# Sheet1.net
KiCad netlist of a schematic drawn in Altium Designer
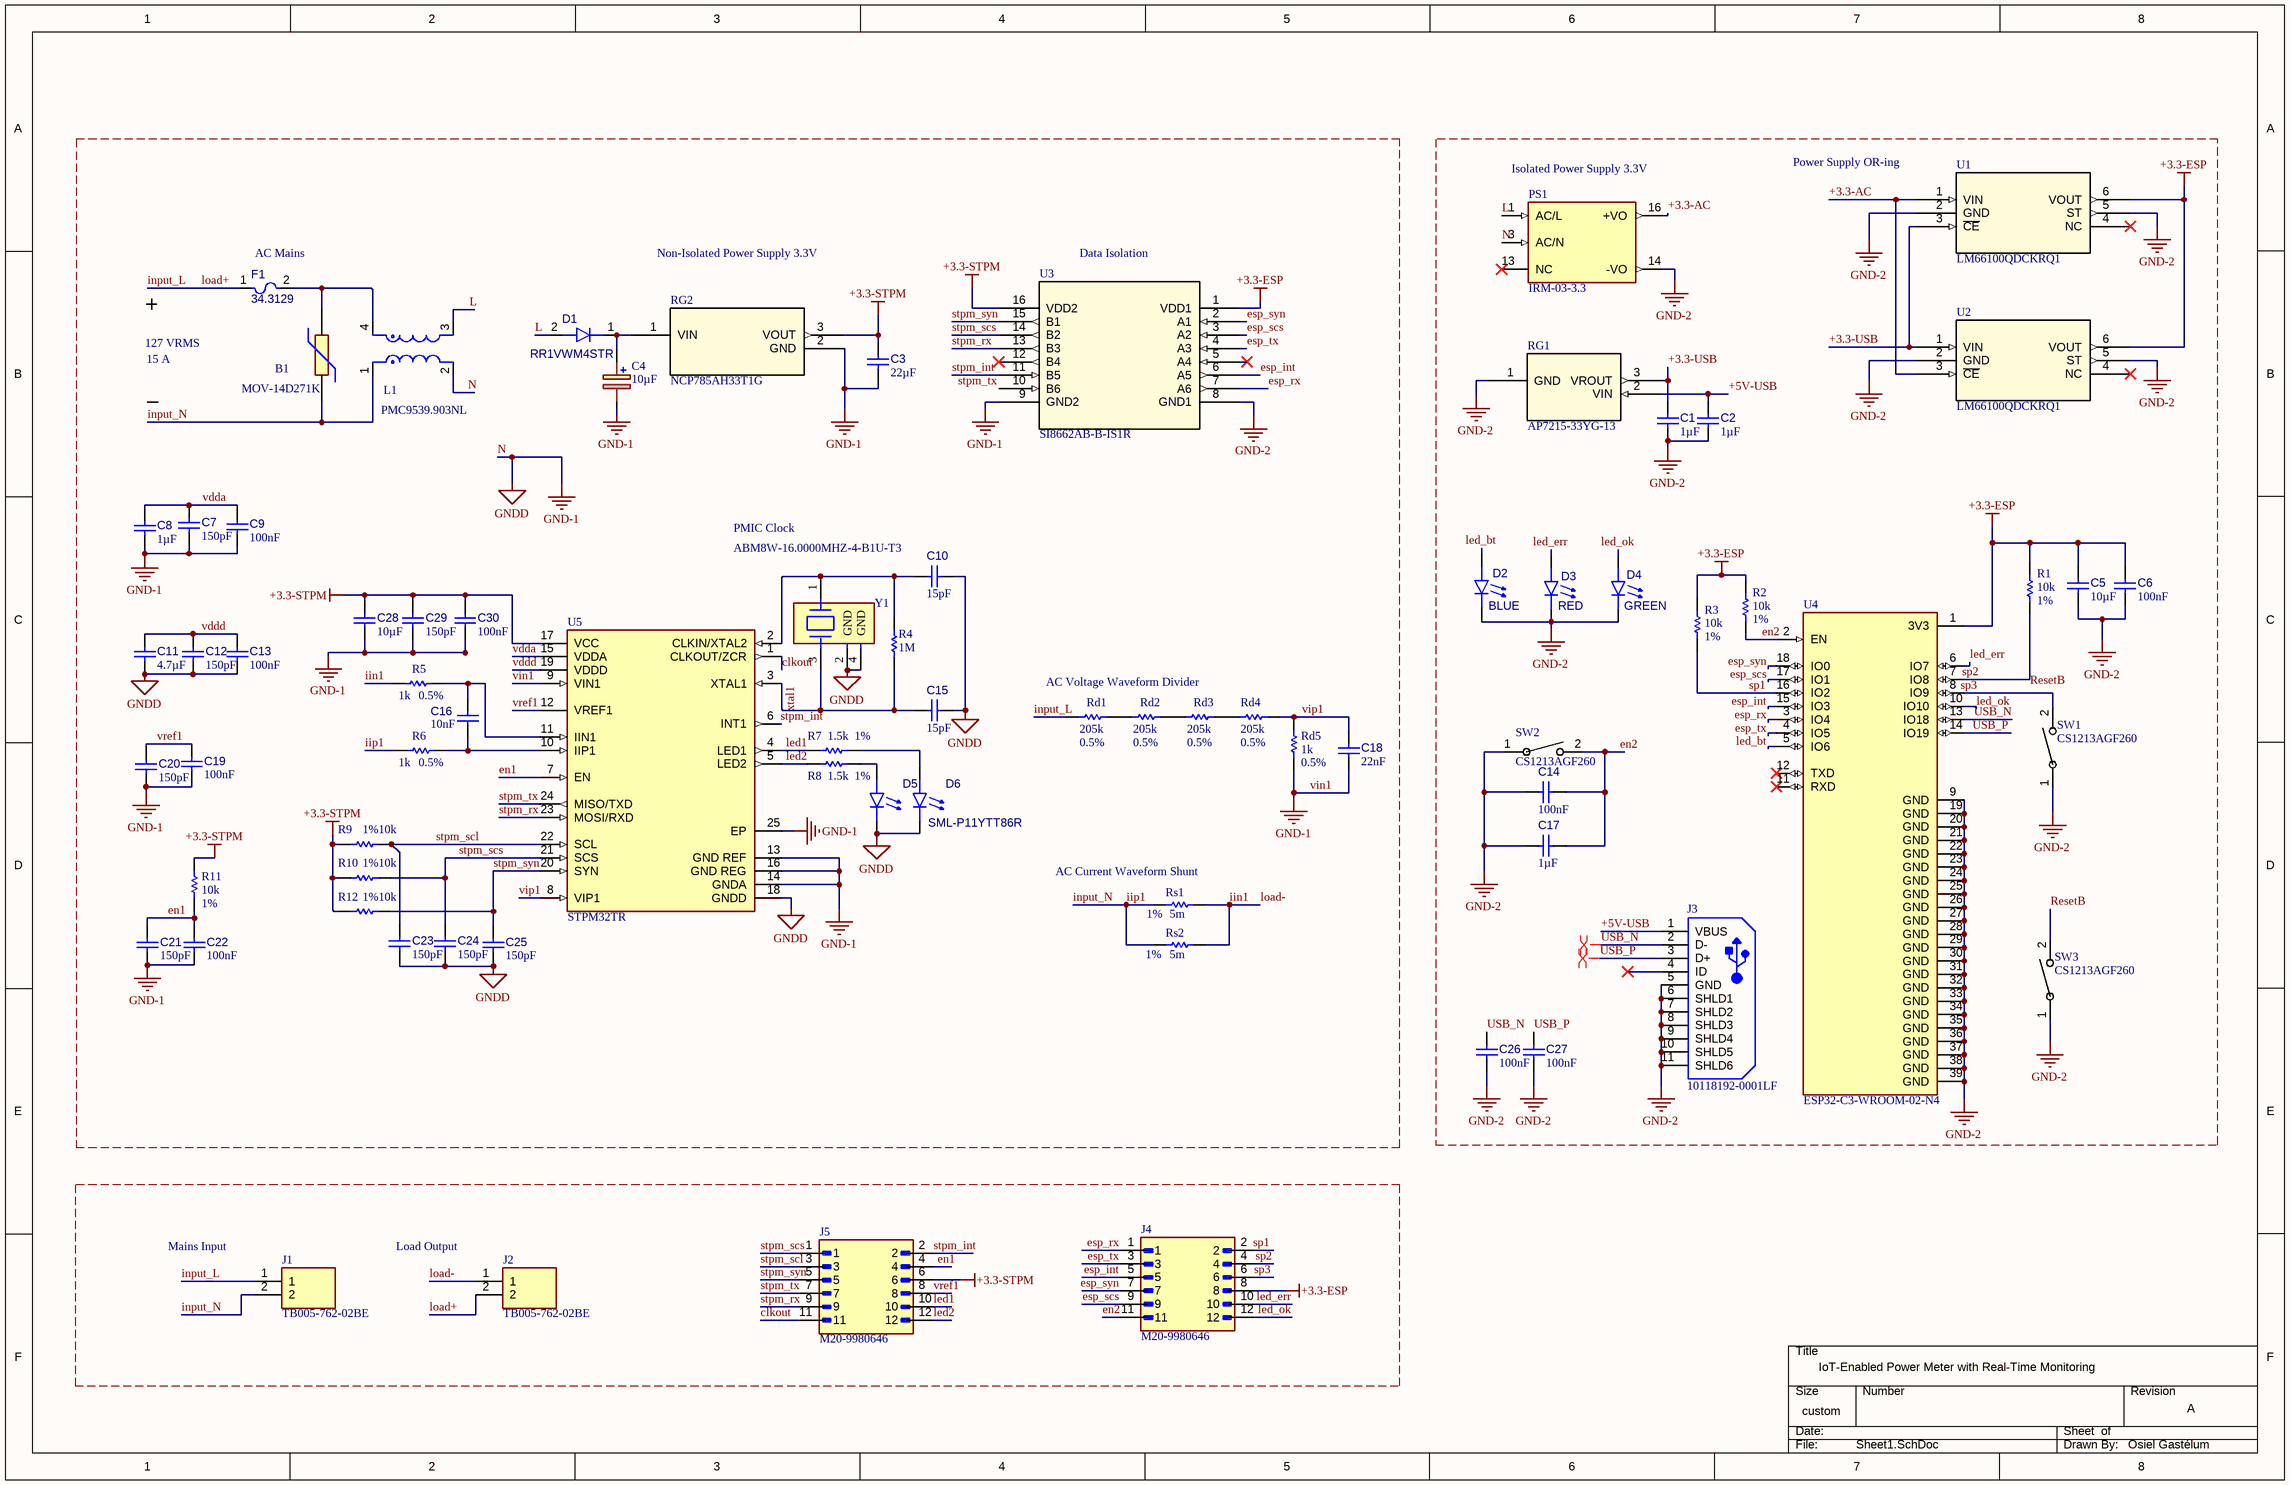
[diagram p0: Sheet1.SchDoc]

(export (version "E")
  (design (tool "Eeschema 10.0.6"))
  (components
    (comp (ref "B1")
      (value "MOV-14D271K")
      (footprint "MOV14D271K")
      (description "Var MOV 175VAC/225VDC 4500A 270V Thru-Hole Radial Bulk")
      (libsource (lib "Workspace") (part "MOV-14D271K"))
    )
    (comp (ref "C1")
      (value "1µF")
      (footprint "CAP_0805_N")
      (description "Multilayer Ceramic Capacitors MLCC – SMD/SMT; KEMET; C0805C105K3RACTU; 1 µF; 0805; 25 V; 25 V")
      (fields (field (name "TOLERANCE") "10%") (field (name "Comment") "CAP-NP-2"))
      (libsource (lib "Workspace") (part "CAP-NP-2"))
    )
    (comp (ref "C2")
      (value "1µF")
      (footprint "CAP_0805_N")
      (description "Multilayer Ceramic Capacitors MLCC – SMD/SMT; KEMET; C0805C105K3RACTU; 1 µF; 0805; 25 V; 25 V")
      (fields (field (name "TOLERANCE") "10%") (field (name "Comment") "CAP-NP-2"))
      (libsource (lib "Workspace") (part "CAP-NP-2"))
    )
    (comp (ref "C3")
      (value "22µF")
      (footprint "CAP_0805_N")
      (description "25V 22uF X5R ±20% 0805 Multilayer Ceramic Capacitors MLCC - SMD/SMT ROHS")
      (fields (field (name "TOLERANCE") "20%") (field (name "Comment") "GRM21BR61E226ME44L"))
      (libsource (lib "Workspace") (part "CAP-NP-2"))
    )
    (comp (ref "C4")
      (value "10µF")
      (footprint "CAPAE1030X1400N")
      (fields (field (name "Comment") "AEF1013100M400R"))
      (libsource (lib "Workspace") (part "AEF1013100M400R-Symbol-1"))
    )
    (comp (ref "C5")
      (value "10µF")
      (footprint "CAP_0805_N")
      (description "0805 C 10UF Ceramic Multilayer Capacitor, 25 VDC, +85DEGC, X5R Dielec, +/-10%")
      (fields (field (name "TOLERANCE") "10%") (field (name "Comment") "CAP-NP-2"))
      (libsource (lib "Workspace") (part "CAP-NP-2"))
    )
    (comp (ref "C6")
      (value "100nF")
      (footprint "CAP_0805_N")
      (description "25V 100nF X7R ±10% 0805 Multilayer Ceramic Capacitors MLCC - SMD/SMT ROHS")
      (fields (field (name "TOLERANCE") "10%") (field (name "Comment") "CAP-NP-2"))
      (libsource (lib "Workspace") (part "CAP-NP-2"))
    )
    (comp (ref "C7")
      (value "150pF")
      (footprint "CAP_0805_N")
      (description "SMD Comm C0G 0805 (2012Metric) Ceramic Capacitor 0.079Lx0.049W 2.00mmx1.25mm C0G NP0 ±10% 150pF")
      (fields (field (name "TOLERANCE") "10%") (field (name "Comment") "CAP-NP-2"))
      (libsource (lib "Workspace") (part "CAP-NP-2"))
    )
    (comp (ref "C8")
      (value "1µF")
      (footprint "CAP_0805_N")
      (description "Multilayer Ceramic Capacitors MLCC – SMD/SMT; KEMET; C0805C105K3RACTU; 1 µF; 0805; 25 V; 25 V")
      (fields (field (name "TOLERANCE") "10%") (field (name "Comment") "CAP-NP-2"))
      (libsource (lib "Workspace") (part "CAP-NP-2"))
    )
    (comp (ref "C9")
      (value "100nF")
      (footprint "CAP_0805_N")
      (description "25V 100nF X7R ±10% 0805 Multilayer Ceramic Capacitors MLCC - SMD/SMT ROHS")
      (fields (field (name "TOLERANCE") "10%") (field (name "Comment") "CAP-NP-2"))
      (libsource (lib "Workspace") (part "CAP-NP-2"))
    )
    (comp (ref "C10")
      (value "15pF")
      (footprint "CAP_0805_N")
      (fields (field (name "TOLERANCE") "5%") (field (name "Comment") "CAP-NP-2"))
      (libsource (lib "Workspace") (part "CAP-NP-2"))
    )
    (comp (ref "C11")
      (value "4.7µF")
      (footprint "CAP_0805_N")
      (fields (field (name "Comment") "CAP-NP-2"))
      (libsource (lib "Workspace") (part "CAP-NP-2"))
    )
    (comp (ref "C12")
      (value "150pF")
      (footprint "CAP_0805_N")
      (description "SMD Comm C0G 0805 (2012Metric) Ceramic Capacitor 0.079Lx0.049W 2.00mmx1.25mm C0G NP0 ±10% 150pF")
      (fields (field (name "TOLERANCE") "10%") (field (name "Comment") "CAP-NP-2"))
      (libsource (lib "Workspace") (part "CAP-NP-2"))
    )
    (comp (ref "C13")
      (value "100nF")
      (footprint "CAP_0805_N")
      (description "25V 100nF X7R ±10% 0805 Multilayer Ceramic Capacitors MLCC - SMD/SMT ROHS")
      (fields (field (name "TOLERANCE") "10%") (field (name "Comment") "CAP-NP-2"))
      (libsource (lib "Workspace") (part "CAP-NP-2"))
    )
    (comp (ref "C14")
      (value "100nF")
      (footprint "CAP_0805_N")
      (description "25V 100nF X7R ±10% 0805 Multilayer Ceramic Capacitors MLCC - SMD/SMT ROHS")
      (fields (field (name "TOLERANCE") "10%") (field (name "Comment") "CAP-NP-2"))
      (libsource (lib "Workspace") (part "CAP-NP-2"))
    )
    (comp (ref "C15")
      (value "15pF")
      (footprint "CAP_0805_N")
      (fields (field (name "TOLERANCE") "5%"))
      (libsource (lib "Workspace") (part "CAP-NP-2"))
    )
    (comp (ref "C16")
      (value "10nF")
      (footprint "CAP_0805_N")
      (fields (field (name "Comment") "C0805C103J3GECAUTO"))
      (libsource (lib "Workspace") (part "CAP-NP-2"))
    )
    (comp (ref "C17")
      (value "1µF")
      (footprint "CAP_0805_N")
      (description "Multilayer Ceramic Capacitors MLCC – SMD/SMT; KEMET; C0805C105K3RACTU; 1 µF; 0805; 25 V; 25 V")
      (fields (field (name "TOLERANCE") "10%") (field (name "Comment") "CAP-NP-2"))
      (libsource (lib "Workspace") (part "CAP-NP-2"))
    )
    (comp (ref "C18")
      (value "22nF")
      (footprint "CAP_0805_N")
      (fields (field (name "Comment") "C0805C223J3GEC7210"))
      (libsource (lib "Workspace") (part "CAP-NP-2"))
    )
    (comp (ref "C19")
      (value "100nF")
      (footprint "CAP_0805_N")
      (description "25V 100nF X7R ±10% 0805 Multilayer Ceramic Capacitors MLCC - SMD/SMT ROHS")
      (fields (field (name "TOLERANCE") "10%") (field (name "Comment") "CAP-NP-2"))
      (libsource (lib "Workspace") (part "CAP-NP-2"))
    )
    (comp (ref "C20")
      (value "150pF")
      (footprint "CAP_0805_N")
      (description "SMD Comm C0G 0805 (2012Metric) Ceramic Capacitor 0.079Lx0.049W 2.00mmx1.25mm C0G NP0 ±10% 150pF")
      (fields (field (name "TOLERANCE") "10%") (field (name "Comment") "CAP-NP-2"))
      (libsource (lib "Workspace") (part "CAP-NP-2"))
    )
    (comp (ref "C21")
      (value "150pF")
      (footprint "CAP_0805_N")
      (description "SMD Comm C0G 0805 (2012Metric) Ceramic Capacitor 0.079Lx0.049W 2.00mmx1.25mm C0G NP0 ±10% 150pF")
      (fields (field (name "TOLERANCE") "10%") (field (name "Comment") "CAP-NP-2"))
      (libsource (lib "Workspace") (part "CAP-NP-2"))
    )
    (comp (ref "C22")
      (value "100nF")
      (footprint "CAP_0805_N")
      (description "25V 100nF X7R ±10% 0805 Multilayer Ceramic Capacitors MLCC - SMD/SMT ROHS")
      (fields (field (name "TOLERANCE") "10%") (field (name "Comment") "CAP-NP-2"))
      (libsource (lib "Workspace") (part "CAP-NP-2"))
    )
    (comp (ref "C23")
      (value "150pF")
      (footprint "CAP_0805_N")
      (description "SMD Comm C0G 0805 (2012Metric) Ceramic Capacitor 0.079Lx0.049W 2.00mmx1.25mm C0G NP0 ±10% 150pF")
      (fields (field (name "TOLERANCE") "10%") (field (name "Comment") "CAP-NP-2"))
      (libsource (lib "Workspace") (part "CAP-NP-2"))
    )
    (comp (ref "C24")
      (value "150pF")
      (footprint "CAP_0805_N")
      (description "SMD Comm C0G 0805 (2012Metric) Ceramic Capacitor 0.079Lx0.049W 2.00mmx1.25mm C0G NP0 ±10% 150pF")
      (fields (field (name "TOLERANCE") "10%") (field (name "Comment") "CAP-NP-2"))
      (libsource (lib "Workspace") (part "CAP-NP-2"))
    )
    (comp (ref "C25")
      (value "150pF")
      (footprint "CAP_0805_N")
      (description "SMD Comm C0G 0805 (2012Metric) Ceramic Capacitor 0.079Lx0.049W 2.00mmx1.25mm C0G NP0 ±10% 150pF")
      (fields (field (name "TOLERANCE") "10%") (field (name "Comment") "CAP-NP-2"))
      (libsource (lib "Workspace") (part "CAP-NP-2"))
    )
    (comp (ref "C26")
      (value "100nF")
      (footprint "CAP_0805_N")
      (description "25V 100nF X7R ±10% 0805 Multilayer Ceramic Capacitors MLCC - SMD/SMT ROHS")
      (fields (field (name "TOLERANCE") "10%") (field (name "Comment") "CAP-NP-2"))
      (libsource (lib "Workspace") (part "CAP-NP-2"))
    )
    (comp (ref "C27")
      (value "100nF")
      (footprint "CAP_0805_N")
      (description "25V 100nF X7R ±10% 0805 Multilayer Ceramic Capacitors MLCC - SMD/SMT ROHS")
      (fields (field (name "TOLERANCE") "10%") (field (name "Comment") "CAP-NP-2"))
      (libsource (lib "Workspace") (part "CAP-NP-2"))
    )
    (comp (ref "C28")
      (value "10µF")
      (footprint "CAP_0805_N")
      (description "0805 C 10UF Ceramic Multilayer Capacitor, 25 VDC, +85DEGC, X5R Dielec, +/-10%")
      (fields (field (name "TOLERANCE") "10%") (field (name "Comment") "C0805C106K3PACTU"))
      (libsource (lib "Workspace") (part "CAP-NP-2"))
    )
    (comp (ref "C29")
      (value "150pF")
      (footprint "CAP_0805_N")
      (description "SMD Comm C0G 0805 (2012Metric) Ceramic Capacitor 0.079Lx0.049W 2.00mmx1.25mm C0G NP0 ±10% 150pF")
      (fields (field (name "TOLERANCE") "10%") (field (name "Comment") "C0805C151K3GACTU"))
      (libsource (lib "Workspace") (part "CAP-NP-2"))
    )
    (comp (ref "C30")
      (value "100nF")
      (footprint "CAP_0805_N")
      (description "25V 100nF X7R ±10% 0805 Multilayer Ceramic Capacitors MLCC - SMD/SMT ROHS")
      (fields (field (name "TOLERANCE") "10%") (field (name "Comment") "C0805C104K3RACTU"))
      (libsource (lib "Workspace") (part "CAP-NP-2"))
    )
    (comp (ref "D1")
      (value "RR1VWM4STR")
      (footprint "PMDE_ROM")
      (description "Rectifier Diode, 1 Phase, 1 Element, 1A, 400V V(RRM), Silicon")
      (libsource (lib "Workspace") (part "DIODE-2"))
    )
    (comp (ref "D2")
      (value "BLUE")
      (footprint "WL-SMCW_0805")
      (description "Led, Blue, 470 Nm, 3.2 V, 30 Ma, 145 Mcd Rohs Compliant: Yes")
      (libsource (lib "Workspace") (part "DIODE-LED-2"))
    )
    (comp (ref "D3")
      (value "RED")
      (footprint "WL-SMCW_0805")
      (description "LED Uni-Color Red 630nm 2-Pin Chip 0805(2012Metric) T/R")
      (libsource (lib "Workspace") (part "DIODE-LED-2"))
    )
    (comp (ref "D4")
      (value "GREEN")
      (footprint "WL-SMCW_0805")
      (description "0805, Green Typ.(@20mA): 520nm, 450mcd, 3.2V, 140Â° InGaN")
      (fields (field (name "MP") "150080GS75000") (field (name "MF") "Wurth Electronics"))
      (libsource (lib "Workspace") (part "DIODE-LED-2"))
    )
    (comp (ref "D5")
      (value "SML-P11DTT86R")
      (footprint "LED_SML-P11D_ROM")
      (description "LED orange LED0402 wavelength 605nm light intensity 7.3mcd Front Mounting")
      (libsource (lib "Workspace") (part "DIODE-LED-2"))
    )
    (comp (ref "D6")
      (value "SML-P11YTT86R")
      (footprint "LED_SML-P11D_ROM")
      (description "LED Uni-Color Yellow Chip LED 2-Pin 0402 T/R")
      (libsource (lib "Workspace") (part "DIODE-LED-2"))
    )
    (comp (ref "F1")
      (value "34.3129")
      (footprint "3132873")
      (description "Fuse 5 x 20 mm, 16 A, T, 250 V (AC), 160 A breaking capacity, 0034.3129")
      (libsource (lib "Workspace") (part "FUSE-2"))
    )
    (comp (ref "J1")
      (value "TB005-762-02BE")
      (footprint "CUI_TB005-762-02BE")
      (description "2~24 Poles, Screw Type, Horizontal, 7.62 Pitch, 26~10 (AWG), Terminal Block Connector")
      (fields (field (name "MF") "Same Sky"))
      (libsource (lib "Workspace") (part "TB005-762-02BE"))
    )
    (comp (ref "J2")
      (value "TB005-762-02BE")
      (footprint "CUI_TB005-762-02BE")
      (description "2~24 Poles, Screw Type, Horizontal, 7.62 Pitch, 26~10 (AWG), Terminal Block Connector")
      (fields (field (name "MF") "Same Sky"))
      (libsource (lib "Workspace") (part "TB005-762-02BE"))
    )
    (comp (ref "J3")
      (value "10118192-0001LF")
      (footprint "FCI-10118192-0001LF-5_V")
      (description "Usb Connector, 5 Contact(S), Female, Right Angle, Surface Mount Terminal, Locking, Receptacle")
      (libsource (lib "Workspace") (part "USB-5-6SHLD"))
    )
    (comp (ref "J4")
      (value "M20-9980646")
      (footprint "HARWIN_M20-9980646")
      (description "Board Connector, 12 Contact(s), 1 Row(s), Male, Straight, Solder Terminal")
      (libsource (lib "Workspace") (part "M20-9980646"))
    )
    (comp (ref "J5")
      (value "M20-9980646")
      (footprint "HARWIN_M20-9980646")
      (description "Board Connector, 12 Contact(s), 1 Row(s), Male, Straight, Solder Terminal")
      (libsource (lib "Workspace") (part "M20-9980646"))
    )
    (comp (ref "L1")
      (value "PMC9539.903NL")
      (footprint "PMC9539_PUL")
      (description "250惟@2.1MHz 1.3m惟 2 Plugin, 19.6x17.8mm Common Mode Filters ROHS")
      (libsource (lib "Workspace") (part "TFORM-4"))
    )
    (comp (ref "PS1")
      (value "IRM-03-3.3")
      (footprint "CONV_IRM-03-3.3")
      (description "DC-DC Converter, PCB Mnt, 3W, 3.3V@600mA, IRM-03 Series")
      (fields (field (name "MF") "MEAN WELL USA Inc."))
      (libsource (lib "Workspace") (part "IRM-03-3.3"))
    )
    (comp (ref "R1")
      (value "10k")
      (footprint "RES_0805_N")
      (description "Res Thick Film 0805 10K Ohm 1% 1/8W ±50ppm/°C Molded SMD Paper T/R")
      (fields (field (name "TOLERANCE") "1%") (field (name "Comment") "RE0805FRE0710KL"))
      (libsource (lib "Workspace") (part "RES"))
    )
    (comp (ref "R2")
      (value "10k")
      (footprint "RES_0805_N")
      (description "Res Thick Film 0805 10K Ohm 1% 1/8W ±50ppm/°C Molded SMD Paper T/R")
      (fields (field (name "TOLERANCE") "1%") (field (name "Comment") "RE0805FRE0710KL"))
      (libsource (lib "Workspace") (part "RES"))
    )
    (comp (ref "R3")
      (value "10k")
      (footprint "RES_0805_N")
      (description "Res Thick Film 0805 10K Ohm 1% 1/8W ±50ppm/°C Molded SMD Paper T/R")
      (fields (field (name "TOLERANCE") "1%") (field (name "Comment") "RE0805FRE0710KL"))
      (libsource (lib "Workspace") (part "RES"))
    )
    (comp (ref "R4")
      (value "1M")
      (footprint "RES_0805_N")
      (description "Res, 1M, 1%, 0.125W, 0805, Thick Film Rohs Compliant: Yes")
      (fields (field (name "TOLERANCE") "1%") (field (name "Comment") "RE0805FRE071ML"))
      (libsource (lib "Workspace") (part "RES"))
    )
    (comp (ref "R5")
      (value "1k")
      (footprint "RES_0805_N")
      (description "125mW Thin Film Resistor 150V ±0.5% ±25ppm/℃ 1kΩ 0805 Chip Resistor - Surface Mount ROHS")
      (fields (field (name "TOLERANCE") "0.5%") (field (name "Comment") "RT0805DRD071KL"))
      (libsource (lib "Workspace") (part "RES"))
    )
    (comp (ref "R6")
      (value "1k")
      (footprint "RES_0805_N")
      (description "125mW Thin Film Resistor 150V ±0.5% ±25ppm/℃ 1kΩ 0805 Chip Resistor - Surface Mount ROHS")
      (fields (field (name "TOLERANCE") "0.5%") (field (name "Comment") "RT0805DRD071KL"))
      (libsource (lib "Workspace") (part "RES"))
    )
    (comp (ref "R7")
      (value "1.5k")
      (footprint "RES_0805_N")
      (description "Chip Resistor Precision Grade Thick Film 0805 1.5kOhm 1% Paper T/R")
      (fields (field (name "TOLERANCE") "1%") (field (name "Comment") "RE0805FRE071K5L"))
      (libsource (lib "Workspace") (part "RES"))
    )
    (comp (ref "R8")
      (value "1.5k")
      (footprint "RES_0805_N")
      (description "Chip Resistor Precision Grade Thick Film 0805 1.5kOhm 1% Paper T/R")
      (fields (field (name "TOLERANCE") "1%") (field (name "Comment") "RE0805FRE071K5L"))
      (libsource (lib "Workspace") (part "RES"))
    )
    (comp (ref "R9")
      (value "10k")
      (footprint "RES_0805_N")
      (description "Res Thick Film 0805 10K Ohm 1% 1/8W ±50ppm/°C Molded SMD Paper T/R")
      (fields (field (name "TOLERANCE") "1%") (field (name "Comment") "RE0805FRE0710KL"))
      (libsource (lib "Workspace") (part "RES"))
    )
    (comp (ref "R10")
      (value "10k")
      (footprint "RES_0805_N")
      (description "Res Thick Film 0805 10K Ohm 1% 1/8W ±50ppm/°C Molded SMD Paper T/R")
      (fields (field (name "TOLERANCE") "1%") (field (name "Comment") "RE0805FRE0710KL"))
      (libsource (lib "Workspace") (part "RES"))
    )
    (comp (ref "R11")
      (value "10k")
      (footprint "RES_0805_N")
      (description "Res Thick Film 0805 10K Ohm 1% 1/8W ±50ppm/°C Molded SMD Paper T/R")
      (fields (field (name "TOLERANCE") "1%") (field (name "Comment") "RE0805FRE0710KL"))
      (libsource (lib "Workspace") (part "RES"))
    )
    (comp (ref "R12")
      (value "10k")
      (footprint "RES_0805_N")
      (description "Res Thick Film 0805 10K Ohm 1% 1/8W ±50ppm/°C Molded SMD Paper T/R")
      (fields (field (name "TOLERANCE") "1%") (field (name "Comment") "RE0805FRE0710KL"))
      (libsource (lib "Workspace") (part "RES"))
    )
    (comp (ref "Rd1")
      (value "205k")
      (footprint "RES_0805_N")
      (description "Res Thin Film 0805 205K Ohm 0.5% 0.125W(1/8W) ±25ppm/C Pad SMD Automotive T/R")
      (fields (field (name "TOLERANCE") "0.5%") (field (name "Comment") "ERA-6AED2053V"))
      (libsource (lib "Workspace") (part "RES"))
    )
    (comp (ref "Rd2")
      (value "205k")
      (footprint "RES_0805_N")
      (description "Res Thin Film 0805 205K Ohm 0.5% 0.125W(1/8W) ±25ppm/C Pad SMD Automotive T/R")
      (fields (field (name "TOLERANCE") "0.5%") (field (name "Comment") "ERA-6AED2053V"))
      (libsource (lib "Workspace") (part "RES"))
    )
    (comp (ref "Rd3")
      (value "205k")
      (footprint "RES_0805_N")
      (description "Res Thin Film 0805 205K Ohm 0.5% 0.125W(1/8W) ±25ppm/C Pad SMD Automotive T/R")
      (fields (field (name "TOLERANCE") "0.5%") (field (name "Comment") "ERA-6AED2053V"))
      (libsource (lib "Workspace") (part "RES"))
    )
    (comp (ref "Rd4")
      (value "205k")
      (footprint "RES_0805_N")
      (description "Res Thin Film 0805 205K Ohm 0.5% 0.125W(1/8W) ±25ppm/C Pad SMD Automotive T/R")
      (fields (field (name "TOLERANCE") "0.5%") (field (name "Comment") "ERA-6AED2053V"))
      (libsource (lib "Workspace") (part "RES"))
    )
    (comp (ref "Rd5")
      (value "1k")
      (footprint "RES_0805_N")
      (description "125mW Thin Film Resistor 150V ±0.5% ±25ppm/℃ 1kΩ 0805 Chip Resistor - Surface Mount ROHS")
      (fields (field (name "TOLERANCE") "0.5%") (field (name "Comment") "RT0805DRD071KL"))
      (libsource (lib "Workspace") (part "RES"))
    )
    (comp (ref "RG1")
      (value "AP7215-33YG-13")
      (footprint "SOT-89-3_2P7X4P7_ONS-M")
      (description "Voltage Regulators, LDO, SOT89-3L 3.3V/0.6A 250MV 3.3-5.5V 1.2V")
      (libsource (lib "Workspace") (part "AP7215-33YG-13-Symbol-1"))
    )
    (comp (ref "RG2")
      (value "NCP785AH33T1G")
      (footprint "SOT-89-3_2P7X4P7_ONS-M")
      (description "NCP785A Series 3.3 V 10 mA High Performance Linear Regulator - SOT-89")
      (libsource (lib "Workspace") (part "NCP785AH33T1G-Symbol-1"))
    )
    (comp (ref "Rs1")
      (value "5m")
      (footprint "RESC6430X100N")
      (description "Fixed Resistor, 5W, 0.005ohm, 0.158V, 1% +/-Tol, 50ppm/Cel, Surface Mount, 2512")
      (fields (field (name "TOLERANCE") "1%") (field (name "Comment") "CSSU2512FT5L00"))
      (libsource (lib "Workspace") (part "RES"))
    )
    (comp (ref "Rs2")
      (value "5m")
      (footprint "RESC6430X100N")
      (description "Fixed Resistor, 5W, 0.005ohm, 0.158V, 1% +/-Tol, 50ppm/Cel, Surface Mount, 2512")
      (fields (field (name "TOLERANCE") "1%") (field (name "Comment") "CSSU2512FT5L00"))
      (libsource (lib "Workspace") (part "RES"))
    )
    (comp (ref "SW1")
      (value "CS1213AGF260")
      (footprint "SW_CS1213AGF260_CRS")
      (description "Description")
      (fields (field (name "COPYRIGHT") "Copyright (C) 2025 Ultra Librarian. All rights reserved."))
      (libsource (lib "Workspace") (part "CS1213AGF260"))
    )
    (comp (ref "SW2")
      (value "CS1213AGF260")
      (footprint "SW_CS1213AGF260_CRS")
      (description "Description")
      (fields (field (name "COPYRIGHT") "Copyright (C) 2025 Ultra Librarian. All rights reserved."))
      (libsource (lib "") (part "CS1213AGF260_1"))
    )
    (comp (ref "SW3")
      (value "CS1213AGF260")
      (footprint "SW_CS1213AGF260_CRS")
      (description "Description")
      (fields (field (name "COPYRIGHT") "Copyright (C) 2025 Ultra Librarian. All rights reserved."))
      (libsource (lib "Workspace") (part "CS1213AGF260"))
    )
    (comp (ref "U1")
      (value "LM66100QDCKRQ1")
      (footprint "SC70-6_DCK_TEX")
      (description "Automotive 1.5-V to 5.5-V, 1.5-A, 0.5-µA IQ ideal diode with integrated FET 6-SC70 -40 to 125")
      (libsource (lib "Workspace") (part "LM66100QDCKRQ1-Symbol-1"))
    )
    (comp (ref "U2")
      (value "LM66100QDCKRQ1")
      (footprint "SC70-6_DCK_TEX")
      (description "Automotive 1.5-V to 5.5-V, 1.5-A, 0.5-µA IQ ideal diode with integrated FET 6-SC70 -40 to 125")
      (libsource (lib "Workspace") (part "LM66100QDCKRQ1-Symbol-1"))
    )
    (comp (ref "U3")
      (value "SI8662AB-B-IS1R")
      (footprint "SOIC-16_SIL")
      (description "General Purpose tal Isolator 2500Vrms 6 Channel 1Mbps 35kV/µs CMTI 16-SOIC (0.154 , 3.90mm Width)")
      (libsource (lib "Workspace") (part "SI8662AB-B-IS1R"))
    )
    (comp (ref "U4")
      (value "ESP32-C3-WROOM-02-N4")
      (footprint "MODULE_ESP32-C3-WROOM-02-H4")
      (fields (field (name "MF") "Espressif Systems"))
      (libsource (lib "Workspace") (part "ESP32-C3-WROOM-02-N4"))
    )
    (comp (ref "U5")
      (value "STPM32TR")
      (footprint "FP-QFN24L-7596209-IPC_B")
      (description "STPM32 Series 3.3 V 4.3 mA 3.6 kHz Single Phase Metering IC - QFN-24")
      (libsource (lib "Workspace") (part "5b5f0ec8f2a583f794e357655103e6c"))
    )
    (comp (ref "Y1")
      (value "ABM8W-16.0000MHZ-4-B1U-T3")
      (footprint "FP-ABM8W-MFG")
      (description "Crystal 16MHz ±10ppm (Tol) ±10ppm (Stability) 4pF FUND 70Ohm 4-Pin SMD T/R")
      (libsource (lib "Workspace") (part "41079aabb0e87794b56622915be14ed"))
    )
  )
  (nets
    (net (code "1") (name "+3.3-ESP") (class "Default")
      (node (ref "C5") (pin "1") (pinfunction "1_1") (pintype "passive"))
      (node (ref "C6") (pin "2") (pinfunction "2_2") (pintype "passive"))
      (node (ref "J4") (pin "8") (pinfunction "8_8") (pintype "passive"))
      (node (ref "R1") (pin "1") (pinfunction "1_1") (pintype "passive"))
      (node (ref "R2") (pin "1") (pinfunction "1_1") (pintype "passive"))
      (node (ref "R3") (pin "1") (pinfunction "1_1") (pintype "passive"))
      (node (ref "U1") (pin "6") (pinfunction "VOUT_6") (pintype "output"))
      (node (ref "U2") (pin "6") (pinfunction "VOUT_6") (pintype "output"))
      (node (ref "U3") (pin "1") (pinfunction "VDD1_1") (pintype "power_in"))
      (node (ref "U4") (pin "1") (pinfunction "3V3_1") (pintype "power_in"))
    )
    (net (code "2") (name "+3.3-STPM") (class "Default")
      (node (ref "C28") (pin "2") (pinfunction "2_2") (pintype "passive"))
      (node (ref "C29") (pin "2") (pinfunction "2_2") (pintype "passive"))
      (node (ref "C3") (pin "2") (pinfunction "2_2") (pintype "passive"))
      (node (ref "C30") (pin "2") (pinfunction "2_2") (pintype "passive"))
      (node (ref "J5") (pin "6") (pinfunction "6_6") (pintype "passive"))
      (node (ref "R10") (pin "2") (pinfunction "2_2") (pintype "passive"))
      (node (ref "R11") (pin "2") (pinfunction "2_2") (pintype "passive"))
      (node (ref "R12") (pin "2") (pinfunction "2_2") (pintype "passive"))
      (node (ref "R9") (pin "2") (pinfunction "2_2") (pintype "passive"))
      (node (ref "RG2") (pin "3") (pinfunction "VOUT_3") (pintype "output"))
      (node (ref "U3") (pin "16") (pinfunction "VDD2_16") (pintype "power_in"))
      (node (ref "U5") (pin "17") (pinfunction "VCC_17") (pintype "power_in"))
    )
    (net (code "3") (name "/+3.3-AC") (class "Default")
      (node (ref "PS1") (pin "16") (pinfunction "+VO_16") (pintype "output"))
      (node (ref "U1") (pin "1") (pinfunction "VIN_1") (pintype "input"))
      (node (ref "U2") (pin "3") (pinfunction "~{CE}_3") (pintype "input"))
    )
    (net (code "4") (name "/+3.3-USB") (class "Default")
      (node (ref "C1") (pin "2") (pinfunction "2_2") (pintype "passive"))
      (node (ref "RG1") (pin "3") (pinfunction "VROUT_3") (pintype "output"))
      (node (ref "U1") (pin "3") (pinfunction "~{CE}_3") (pintype "input"))
      (node (ref "U2") (pin "1") (pinfunction "VIN_1") (pintype "input"))
    )
    (net (code "5") (name "/+5V-USB") (class "Default")
      (node (ref "C2") (pin "2") (pinfunction "2_2") (pintype "passive"))
      (node (ref "J3") (pin "1") (pinfunction "VBUS_1") (pintype "passive"))
      (node (ref "RG1") (pin "2") (pinfunction "VIN_2") (pintype "input"))
    )
    (net (code "6") (name "/L") (class "Default")
      (node (ref "D1") (pin "2") (pinfunction "A_2") (pintype "passive"))
      (node (ref "L1") (pin "3") (pinfunction "3_3") (pintype "passive"))
      (node (ref "PS1") (pin "1") (pinfunction "AC/L_1") (pintype "input"))
    )
    (net (code "7") (name "/ResetB") (class "Default")
      (node (ref "J4") (pin "4") (pinfunction "4_4") (pintype "passive"))
      (node (ref "R1") (pin "2") (pinfunction "2_2") (pintype "passive"))
      (node (ref "SW3") (pin "2") (pinfunction "2_2") (pintype "passive"))
      (node (ref "U4") (pin "7") (pinfunction "IO8_7") (pintype "bidirectional"))
    )
    (net (code "8") (name "/USB_N") (class "Default")
      (node (ref "C26") (pin "2") (pinfunction "2_2") (pintype "passive"))
      (node (ref "J3") (pin "2") (pinfunction "D-_2") (pintype "passive"))
      (node (ref "U4") (pin "13") (pinfunction "IO18_13") (pintype "bidirectional"))
    )
    (net (code "9") (name "/USB_P") (class "Default")
      (node (ref "C27") (pin "2") (pinfunction "2_2") (pintype "passive"))
      (node (ref "J3") (pin "3") (pinfunction "D+_3") (pintype "passive"))
      (node (ref "U4") (pin "14") (pinfunction "IO19_14") (pintype "bidirectional"))
    )
    (net (code "10") (name "/clkout") (class "Default")
      (node (ref "J5") (pin "11") (pinfunction "11_11") (pintype "passive"))
      (node (ref "U5") (pin "1") (pinfunction "CLKOUT/ZCR_1") (pintype "output"))
    )
    (net (code "11") (name "/en1") (class "Default")
      (node (ref "C21") (pin "2") (pinfunction "2_2") (pintype "passive"))
      (node (ref "C22") (pin "2") (pinfunction "2_2") (pintype "passive"))
      (node (ref "J5") (pin "4") (pinfunction "4_4") (pintype "passive"))
      (node (ref "R11") (pin "1") (pinfunction "1_1") (pintype "passive"))
      (node (ref "U5") (pin "7") (pinfunction "EN_7") (pintype "input"))
    )
    (net (code "12") (name "/en2") (class "Default")
      (node (ref "C14") (pin "1") (pinfunction "1_1") (pintype "passive"))
      (node (ref "C17") (pin "2") (pinfunction "2_2") (pintype "passive"))
      (node (ref "J4") (pin "11") (pinfunction "11_11") (pintype "passive"))
      (node (ref "R2") (pin "2") (pinfunction "2_2") (pintype "passive"))
      (node (ref "SW2") (pin "2") (pinfunction "2_2") (pintype "passive"))
      (node (ref "U4") (pin "2") (pinfunction "EN_2") (pintype "input"))
    )
    (net (code "13") (name "/esp_int") (class "Default")
      (node (ref "J4") (pin "5") (pinfunction "5_5") (pintype "passive"))
      (node (ref "U3") (pin "6") (pinfunction "A5_6") (pintype "output"))
      (node (ref "U4") (pin "15") (pinfunction "IO3_15") (pintype "bidirectional"))
    )
    (net (code "14") (name "/esp_rx") (class "Default")
      (node (ref "J4") (pin "1") (pinfunction "1_1") (pintype "passive"))
      (node (ref "U3") (pin "7") (pinfunction "A6_7") (pintype "output"))
      (node (ref "U4") (pin "3") (pinfunction "IO4_3") (pintype "bidirectional"))
    )
    (net (code "15") (name "/esp_scs") (class "Default")
      (node (ref "J4") (pin "9") (pinfunction "9_9") (pintype "passive"))
      (node (ref "U3") (pin "3") (pinfunction "A2_3") (pintype "input"))
      (node (ref "U4") (pin "17") (pinfunction "IO1_17") (pintype "bidirectional"))
    )
    (net (code "16") (name "/esp_syn") (class "Default")
      (node (ref "J4") (pin "7") (pinfunction "7_7") (pintype "passive"))
      (node (ref "U3") (pin "2") (pinfunction "A1_2") (pintype "input"))
      (node (ref "U4") (pin "18") (pinfunction "IO0_18") (pintype "bidirectional"))
    )
    (net (code "17") (name "/esp_tx") (class "Default")
      (node (ref "J4") (pin "3") (pinfunction "3_3") (pintype "passive"))
      (node (ref "U3") (pin "4") (pinfunction "A3_4") (pintype "input"))
      (node (ref "U4") (pin "4") (pinfunction "IO5_4") (pintype "bidirectional"))
    )
    (net (code "18") (name "/iin1") (class "Default")
      (node (ref "J2") (pin "1") (pinfunction "1_1") (pintype "passive"))
      (node (ref "R5") (pin "1") (pinfunction "1_1") (pintype "passive"))
      (node (ref "Rs1") (pin "2") (pinfunction "2_2") (pintype "passive"))
      (node (ref "Rs2") (pin "2") (pinfunction "2_2") (pintype "passive"))
    )
    (net (code "19") (name "/iip1") (class "Default")
      (node (ref "B1") (pin "1") (pinfunction "1_1") (pintype "passive"))
      (node (ref "J1") (pin "2") (pinfunction "2_2") (pintype "passive"))
      (node (ref "L1") (pin "1") (pinfunction "1_1") (pintype "passive"))
      (node (ref "R6") (pin "1") (pinfunction "1_1") (pintype "passive"))
      (node (ref "Rs1") (pin "1") (pinfunction "1_1") (pintype "passive"))
      (node (ref "Rs2") (pin "1") (pinfunction "1_1") (pintype "passive"))
    )
    (net (code "20") (name "/input_L") (class "Default")
      (node (ref "F1") (pin "1") (pinfunction "1_1") (pintype "passive"))
      (node (ref "J1") (pin "1") (pinfunction "1_1") (pintype "passive"))
      (node (ref "J2") (pin "2") (pinfunction "2_2") (pintype "passive"))
      (node (ref "Rd1") (pin "1") (pinfunction "1_1") (pintype "passive"))
    )
    (net (code "21") (name "/led1") (class "Default")
      (node (ref "J5") (pin "10") (pinfunction "10_10") (pintype "passive"))
      (node (ref "R7") (pin "1") (pinfunction "1_1") (pintype "passive"))
      (node (ref "U5") (pin "4") (pinfunction "LED1_4") (pintype "output"))
    )
    (net (code "22") (name "/led2") (class "Default")
      (node (ref "J5") (pin "12") (pinfunction "12_12") (pintype "passive"))
      (node (ref "R8") (pin "1") (pinfunction "1_1") (pintype "passive"))
      (node (ref "U5") (pin "5") (pinfunction "LED2_5") (pintype "output"))
    )
    (net (code "23") (name "/led_bt") (class "Default")
      (node (ref "D2") (pin "2") (pinfunction "A_2") (pintype "passive"))
      (node (ref "U4") (pin "5") (pinfunction "IO6_5") (pintype "bidirectional"))
    )
    (net (code "24") (name "/led_err") (class "Default")
      (node (ref "D3") (pin "2") (pinfunction "A_2") (pintype "passive"))
      (node (ref "J4") (pin "10") (pinfunction "10_10") (pintype "passive"))
      (node (ref "U4") (pin "6") (pinfunction "IO7_6") (pintype "bidirectional"))
    )
    (net (code "25") (name "/led_ok") (class "Default")
      (node (ref "D4") (pin "2") (pinfunction "A_2") (pintype "passive"))
      (node (ref "J4") (pin "12") (pinfunction "12_12") (pintype "passive"))
      (node (ref "U4") (pin "10") (pinfunction "IO10_10") (pintype "bidirectional"))
    )
    (net (code "26") (name "/sp1") (class "Default")
      (node (ref "J4") (pin "2") (pinfunction "2_2") (pintype "passive"))
      (node (ref "R3") (pin "2") (pinfunction "2_2") (pintype "passive"))
      (node (ref "U4") (pin "16") (pinfunction "IO2_16") (pintype "bidirectional"))
    )
    (net (code "27") (name "/sp3") (class "Default")
      (node (ref "J4") (pin "6") (pinfunction "6_6") (pintype "passive"))
      (node (ref "SW1") (pin "2") (pinfunction "2_2") (pintype "passive"))
      (node (ref "U4") (pin "8") (pinfunction "IO9_8") (pintype "bidirectional"))
    )
    (net (code "28") (name "/stpm_int") (class "Default")
      (node (ref "J5") (pin "2") (pinfunction "2_2") (pintype "passive"))
      (node (ref "U3") (pin "11") (pinfunction "B5_11") (pintype "input"))
      (node (ref "U5") (pin "6") (pinfunction "INT1_6") (pintype "output"))
    )
    (net (code "29") (name "/stpm_rx") (class "Default")
      (node (ref "J5") (pin "9") (pinfunction "9_9") (pintype "passive"))
      (node (ref "U3") (pin "13") (pinfunction "B3_13") (pintype "output"))
      (node (ref "U5") (pin "23") (pinfunction "MOSI/RXD_23") (pintype "input"))
    )
    (net (code "30") (name "/stpm_scl") (class "Default")
      (node (ref "C23") (pin "2") (pinfunction "2_2") (pintype "passive"))
      (node (ref "J5") (pin "3") (pinfunction "3_3") (pintype "passive"))
      (node (ref "R9") (pin "1") (pinfunction "1_1") (pintype "passive"))
      (node (ref "U5") (pin "22") (pinfunction "SCL_22") (pintype "input"))
    )
    (net (code "31") (name "/stpm_scs") (class "Default")
      (node (ref "C24") (pin "2") (pinfunction "2_2") (pintype "passive"))
      (node (ref "J5") (pin "1") (pinfunction "1_1") (pintype "passive"))
      (node (ref "R10") (pin "1") (pinfunction "1_1") (pintype "passive"))
      (node (ref "U3") (pin "14") (pinfunction "B2_14") (pintype "output"))
      (node (ref "U5") (pin "21") (pinfunction "SCS_21") (pintype "input"))
    )
    (net (code "32") (name "/stpm_syn") (class "Default")
      (node (ref "C25") (pin "2") (pinfunction "2_2") (pintype "passive"))
      (node (ref "J5") (pin "5") (pinfunction "5_5") (pintype "passive"))
      (node (ref "R12") (pin "1") (pinfunction "1_1") (pintype "passive"))
      (node (ref "U3") (pin "15") (pinfunction "B1_15") (pintype "output"))
      (node (ref "U5") (pin "20") (pinfunction "SYN_20") (pintype "input"))
    )
    (net (code "33") (name "/stpm_tx") (class "Default")
      (node (ref "J5") (pin "7") (pinfunction "7_7") (pintype "passive"))
      (node (ref "U3") (pin "10") (pinfunction "B6_10") (pintype "input"))
      (node (ref "U5") (pin "24") (pinfunction "MISO/TXD_24") (pintype "output"))
    )
    (net (code "34") (name "/vdda") (class "Default")
      (node (ref "C7") (pin "2") (pinfunction "2_2") (pintype "passive"))
      (node (ref "C8") (pin "2") (pinfunction "2_2") (pintype "passive"))
      (node (ref "C9") (pin "2") (pinfunction "2_2") (pintype "passive"))
      (node (ref "U5") (pin "15") (pinfunction "VDDA_15") (pintype "power_in"))
    )
    (net (code "35") (name "/vddd") (class "Default")
      (node (ref "C11") (pin "2") (pinfunction "2_2") (pintype "passive"))
      (node (ref "C12") (pin "2") (pinfunction "2_2") (pintype "passive"))
      (node (ref "C13") (pin "2") (pinfunction "2_2") (pintype "passive"))
      (node (ref "U5") (pin "19") (pinfunction "VDDD_19") (pintype "power_in"))
    )
    (net (code "36") (name "/vip1") (class "Default")
      (node (ref "C18") (pin "2") (pinfunction "2_2") (pintype "passive"))
      (node (ref "Rd4") (pin "1") (pinfunction "1_1") (pintype "passive"))
      (node (ref "Rd5") (pin "1") (pinfunction "1_1") (pintype "passive"))
      (node (ref "U5") (pin "8") (pinfunction "VIP1_8") (pintype "input"))
    )
    (net (code "37") (name "/vref1") (class "Default")
      (node (ref "C19") (pin "2") (pinfunction "2_2") (pintype "passive"))
      (node (ref "C20") (pin "2") (pinfunction "2_2") (pintype "passive"))
      (node (ref "J5") (pin "8") (pinfunction "8_8") (pintype "passive"))
      (node (ref "U5") (pin "12") (pinfunction "VREF1_12") (pintype "power_in"))
    )
    (net (code "38") (name "/xtal1") (class "Default")
      (node (ref "C15") (pin "2") (pinfunction "2_2") (pintype "passive"))
      (node (ref "R4") (pin "1") (pinfunction "1_1") (pintype "passive"))
      (node (ref "U5") (pin "3") (pinfunction "XTAL1_3") (pintype "input"))
      (node (ref "Y1") (pin "3") (pinfunction "3_3") (pintype "passive"))
    )
    (net (code "39") (name "GND-1") (class "Default")
      (node (ref "C10") (pin "1") (pinfunction "1_1") (pintype "passive"))
      (node (ref "C11") (pin "1") (pinfunction "1_1") (pintype "passive"))
      (node (ref "C12") (pin "1") (pinfunction "1_1") (pintype "passive"))
      (node (ref "C13") (pin "1") (pinfunction "1_1") (pintype "passive"))
      (node (ref "C15") (pin "1") (pinfunction "1_1") (pintype "passive"))
      (node (ref "C18") (pin "1") (pinfunction "1_1") (pintype "passive"))
      (node (ref "C19") (pin "1") (pinfunction "1_1") (pintype "passive"))
      (node (ref "C20") (pin "1") (pinfunction "1_1") (pintype "passive"))
      (node (ref "C21") (pin "1") (pinfunction "1_1") (pintype "passive"))
      (node (ref "C22") (pin "1") (pinfunction "1_1") (pintype "passive"))
      (node (ref "C23") (pin "1") (pinfunction "1_1") (pintype "passive"))
      (node (ref "C24") (pin "1") (pinfunction "1_1") (pintype "passive"))
      (node (ref "C25") (pin "1") (pinfunction "1_1") (pintype "passive"))
      (node (ref "C28") (pin "1") (pinfunction "1_1") (pintype "passive"))
      (node (ref "C29") (pin "1") (pinfunction "1_1") (pintype "passive"))
      (node (ref "C3") (pin "1") (pinfunction "1_1") (pintype "passive"))
      (node (ref "C30") (pin "1") (pinfunction "1_1") (pintype "passive"))
      (node (ref "C4") (pin "2") (pinfunction "-_2") (pintype "passive"))
      (node (ref "C7") (pin "1") (pinfunction "1_1") (pintype "passive"))
      (node (ref "C8") (pin "1") (pinfunction "1_1") (pintype "passive"))
      (node (ref "C9") (pin "1") (pinfunction "1_1") (pintype "passive"))
      (node (ref "D5") (pin "1") (pinfunction "K_1") (pintype "passive"))
      (node (ref "D6") (pin "1") (pinfunction "K_1") (pintype "passive"))
      (node (ref "L1") (pin "2") (pinfunction "2_2") (pintype "passive"))
      (node (ref "PS1") (pin "3") (pinfunction "AC/N_3") (pintype "input"))
      (node (ref "RG2") (pin "2") (pinfunction "GND_2") (pintype "power_in"))
      (node (ref "Rd5") (pin "2") (pinfunction "2_2") (pintype "passive"))
      (node (ref "U3") (pin "9") (pinfunction "GND2_9") (pintype "power_in"))
      (node (ref "U5") (pin "13") (pinfunction "GND_REF_13") (pintype "power_in"))
      (node (ref "U5") (pin "14") (pinfunction "GNDA_14") (pintype "power_in"))
      (node (ref "U5") (pin "16") (pinfunction "GND_REG_16") (pintype "power_in"))
      (node (ref "U5") (pin "18") (pinfunction "GNDD_18") (pintype "power_in"))
      (node (ref "U5") (pin "25") (pinfunction "EP_25") (pintype "power_in"))
      (node (ref "U5") (pin "9") (pinfunction "VIN1_9") (pintype "input"))
      (node (ref "Y1") (pin "2") (pinfunction "GND_2") (pintype "power_in"))
      (node (ref "Y1") (pin "4") (pinfunction "GND_4") (pintype "power_in"))
    )
    (net (code "40") (name "GND-2") (class "Default")
      (node (ref "C1") (pin "1") (pinfunction "1_1") (pintype "passive"))
      (node (ref "C14") (pin "2") (pinfunction "2_2") (pintype "passive"))
      (node (ref "C17") (pin "1") (pinfunction "1_1") (pintype "passive"))
      (node (ref "C2") (pin "1") (pinfunction "1_1") (pintype "passive"))
      (node (ref "C26") (pin "1") (pinfunction "1_1") (pintype "passive"))
      (node (ref "C27") (pin "1") (pinfunction "1_1") (pintype "passive"))
      (node (ref "C5") (pin "2") (pinfunction "2_2") (pintype "passive"))
      (node (ref "C6") (pin "1") (pinfunction "1_1") (pintype "passive"))
      (node (ref "D2") (pin "1") (pinfunction "K_1") (pintype "passive"))
      (node (ref "D3") (pin "1") (pinfunction "K_1") (pintype "passive"))
      (node (ref "D4") (pin "1") (pinfunction "K_1") (pintype "passive"))
      (node (ref "J3") (pin "10") (pinfunction "SHLD5_10") (pintype "passive"))
      (node (ref "J3") (pin "11") (pinfunction "SHLD6_11") (pintype "passive"))
      (node (ref "J3") (pin "5") (pinfunction "GND_5") (pintype "passive"))
      (node (ref "J3") (pin "6") (pinfunction "SHLD1_6") (pintype "passive"))
      (node (ref "J3") (pin "7") (pinfunction "SHLD2_7") (pintype "passive"))
      (node (ref "J3") (pin "8") (pinfunction "SHLD3_8") (pintype "passive"))
      (node (ref "J3") (pin "9") (pinfunction "SHLD4_9") (pintype "passive"))
      (node (ref "PS1") (pin "14") (pinfunction "-VO_14") (pintype "output"))
      (node (ref "RG1") (pin "1") (pinfunction "GND_1") (pintype "power_in"))
      (node (ref "SW1") (pin "1") (pinfunction "1_1") (pintype "passive"))
      (node (ref "SW2") (pin "1") (pinfunction "1_1") (pintype "passive"))
      (node (ref "SW3") (pin "1") (pinfunction "1_1") (pintype "passive"))
      (node (ref "U1") (pin "2") (pinfunction "GND_2") (pintype "power_in"))
      (node (ref "U1") (pin "5") (pinfunction "ST_5") (pintype "output"))
      (node (ref "U2") (pin "2") (pinfunction "GND_2") (pintype "power_in"))
      (node (ref "U2") (pin "5") (pinfunction "ST_5") (pintype "output"))
      (node (ref "U3") (pin "8") (pinfunction "GND1_8") (pintype "power_in"))
      (node (ref "U4") (pin "19") (pinfunction "GND_19") (pintype "power_in"))
      (node (ref "U4") (pin "20") (pinfunction "GND_20") (pintype "power_in"))
      (node (ref "U4") (pin "21") (pinfunction "GND_21") (pintype "power_in"))
      (node (ref "U4") (pin "22") (pinfunction "GND_22") (pintype "power_in"))
      (node (ref "U4") (pin "23") (pinfunction "GND_23") (pintype "power_in"))
      (node (ref "U4") (pin "24") (pinfunction "GND_24") (pintype "power_in"))
      (node (ref "U4") (pin "25") (pinfunction "GND_25") (pintype "power_in"))
      (node (ref "U4") (pin "26") (pinfunction "GND_26") (pintype "power_in"))
      (node (ref "U4") (pin "27") (pinfunction "GND_27") (pintype "power_in"))
      (node (ref "U4") (pin "28") (pinfunction "GND_28") (pintype "power_in"))
      (node (ref "U4") (pin "29") (pinfunction "GND_29") (pintype "power_in"))
      (node (ref "U4") (pin "30") (pinfunction "GND_30") (pintype "power_in"))
      (node (ref "U4") (pin "31") (pinfunction "GND_31") (pintype "power_in"))
      (node (ref "U4") (pin "32") (pinfunction "GND_32") (pintype "power_in"))
      (node (ref "U4") (pin "33") (pinfunction "GND_33") (pintype "power_in"))
      (node (ref "U4") (pin "34") (pinfunction "GND_34") (pintype "power_in"))
      (node (ref "U4") (pin "35") (pinfunction "GND_35") (pintype "power_in"))
      (node (ref "U4") (pin "36") (pinfunction "GND_36") (pintype "power_in"))
      (node (ref "U4") (pin "37") (pinfunction "GND_37") (pintype "power_in"))
      (node (ref "U4") (pin "38") (pinfunction "GND_38") (pintype "power_in"))
      (node (ref "U4") (pin "39") (pinfunction "GND_39") (pintype "power_in"))
      (node (ref "U4") (pin "9") (pinfunction "GND_9") (pintype "power_in"))
    )
    (net (code "41") (name "Net-(B1-Pad2)") (class "Default")
      (node (ref "B1") (pin "2") (pinfunction "2_2") (pintype "passive"))
      (node (ref "F1") (pin "2") (pinfunction "2_2") (pintype "passive"))
      (node (ref "L1") (pin "4") (pinfunction "4_4") (pintype "passive"))
    )
    (net (code "42") (name "Net-(C4-+)") (class "Default")
      (node (ref "C4") (pin "1") (pinfunction "+_1") (pintype "passive"))
      (node (ref "D1") (pin "1") (pinfunction "K_1") (pintype "passive"))
      (node (ref "RG2") (pin "1") (pinfunction "VIN_1") (pintype "passive"))
    )
    (net (code "43") (name "Net-(D5-A)") (class "Default")
      (node (ref "D5") (pin "2") (pinfunction "A_2") (pintype "passive"))
      (node (ref "R8") (pin "2") (pinfunction "2_2") (pintype "passive"))
    )
    (net (code "44") (name "Net-(D6-A)") (class "Default")
      (node (ref "D6") (pin "2") (pinfunction "A_2") (pintype "passive"))
      (node (ref "R7") (pin "2") (pinfunction "2_2") (pintype "passive"))
    )
    (net (code "45") (name "Net-(Rd1-Pad2)") (class "Default")
      (node (ref "Rd1") (pin "2") (pinfunction "2_2") (pintype "passive"))
      (node (ref "Rd2") (pin "2") (pinfunction "2_2") (pintype "passive"))
    )
    (net (code "46") (name "Net-(Rd2-Pad1)") (class "Default")
      (node (ref "Rd2") (pin "1") (pinfunction "1_1") (pintype "passive"))
      (node (ref "Rd3") (pin "2") (pinfunction "2_2") (pintype "passive"))
    )
    (net (code "47") (name "Net-(Rd3-Pad1)") (class "Default")
      (node (ref "Rd3") (pin "1") (pinfunction "1_1") (pintype "passive"))
      (node (ref "Rd4") (pin "2") (pinfunction "2_2") (pintype "passive"))
    )
    (net (code "48") (name "Net-(U5-CLKIN{slash}XTAL2)") (class "Default")
      (node (ref "C10") (pin "2") (pinfunction "2_2") (pintype "passive"))
      (node (ref "R4") (pin "2") (pinfunction "2_2") (pintype "passive"))
      (node (ref "U5") (pin "2") (pinfunction "CLKIN/XTAL2_2") (pintype "input"))
      (node (ref "Y1") (pin "1") (pinfunction "1_1") (pintype "passive"))
    )
    (net (code "49") (name "Net-(U5-IIN1)") (class "Default")
      (node (ref "C16") (pin "2") (pinfunction "2_2") (pintype "passive"))
      (node (ref "R5") (pin "2") (pinfunction "2_2") (pintype "passive"))
      (node (ref "U5") (pin "11") (pinfunction "IIN1_11") (pintype "input"))
    )
    (net (code "50") (name "Net-(U5-IIP1)") (class "Default")
      (node (ref "C16") (pin "1") (pinfunction "1_1") (pintype "passive"))
      (node (ref "R6") (pin "2") (pinfunction "2_2") (pintype "passive"))
      (node (ref "U5") (pin "10") (pinfunction "IIP1_10") (pintype "input"))
    )
    (net (code "51") (name "unconnected-(J3-ID-Pad4)") (class "Default")
      (node (ref "J3") (pin "4") (pinfunction "ID_4") (pintype "passive+no_connect"))
    )
    (net (code "52") (name "unconnected-(PS1-NC-Pad13)") (class "Default")
      (node (ref "PS1") (pin "13") (pinfunction "NC_13") (pintype "passive+no_connect"))
    )
    (net (code "53") (name "unconnected-(U1-NC-Pad4)") (class "Default")
      (node (ref "U1") (pin "4") (pinfunction "NC_4") (pintype "passive+no_connect"))
    )
    (net (code "54") (name "unconnected-(U2-NC-Pad4)") (class "Default")
      (node (ref "U2") (pin "4") (pinfunction "NC_4") (pintype "passive+no_connect"))
    )
    (net (code "55") (name "unconnected-(U3-A4-Pad5)") (class "Default")
      (node (ref "U3") (pin "5") (pinfunction "A4_5") (pintype "input+no_connect"))
    )
    (net (code "56") (name "unconnected-(U3-B4-Pad12)") (class "Default")
      (node (ref "U3") (pin "12") (pinfunction "B4_12") (pintype "output+no_connect"))
    )
    (net (code "57") (name "unconnected-(U4-RXD-Pad11)") (class "Default")
      (node (ref "U4") (pin "11") (pinfunction "RXD_11") (pintype "bidirectional+no_connect"))
    )
    (net (code "58") (name "unconnected-(U4-TXD-Pad12)") (class "Default")
      (node (ref "U4") (pin "12") (pinfunction "TXD_12") (pintype "bidirectional+no_connect"))
    )
  )
)
